# untitled.net
KiCad netlist of a schematic drawn in EAGLE
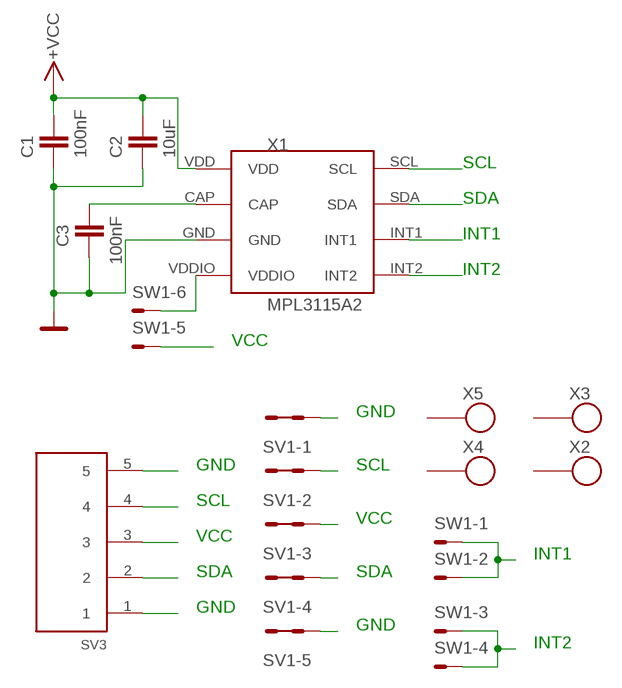
[diagram p0: schematic, sheet 1]

(export (version "E")
  (design (tool "Eeschema 10.0.6"))
  (components
    (comp (ref "C1")
      (value "100nF")
      (footprint "eagle-import:C0805")
      (libsource (lib "eagle-import") (part "C-EUC0805"))
    )
    (comp (ref "C2")
      (value "10uF")
      (footprint "eagle-import:C0805")
      (libsource (lib "eagle-import") (part "C-EUC0805"))
    )
    (comp (ref "C3")
      (value "100nF")
      (footprint "eagle-import:C0805")
      (libsource (lib "eagle-import") (part "C-EUC0805"))
    )
    (comp (ref "SV1")
      (value "MA05-2")
      (footprint "eagle-import:MA05-2")
      (libsource (lib "eagle-import") (part "MA05-2"))
    )
    (comp (ref "SV3")
      (value "SMD_MA05-01")
      (footprint "eagle-import:SMD_MA05-1")
      (libsource (lib "eagle-import") (part "SMD_MA05-01"))
    )
    (comp (ref "SW1")
      (value "MA03-3")
      (footprint "eagle-import:MA03-2")
      (libsource (lib "eagle-import") (part "MA03-3"))
    )
    (comp (ref "X1")
      (value "MPL3115A2")
      (footprint "eagle-import:LGA")
      (libsource (lib "eagle-import") (part "MPL3115A2"))
    )
    (comp (ref "X2")
      (value "SROUB3M")
      (footprint "eagle-import:SROUB3M")
      (libsource (lib "eagle-import") (part "SROUB3M"))
    )
    (comp (ref "X3")
      (value "SROUB3M")
      (footprint "eagle-import:SROUB3M")
      (libsource (lib "eagle-import") (part "SROUB3M"))
    )
    (comp (ref "X4")
      (value "SROUB3M")
      (footprint "eagle-import:SROUB3M")
      (libsource (lib "eagle-import") (part "SROUB3M"))
    )
    (comp (ref "X5")
      (value "SROUB3M")
      (footprint "eagle-import:SROUB3M")
      (libsource (lib "eagle-import") (part "SROUB3M"))
    )
  )
  (nets
    (net (code "1") (name "+VCC") (class "Default")
      (node (ref "C1") (pin "1") (pinfunction "1_1") (pintype "passive"))
      (node (ref "C2") (pin "1") (pinfunction "1_1") (pintype "passive"))
      (node (ref "SV1") (pin "5") (pinfunction "K_5") (pintype "passive"))
      (node (ref "SV1") (pin "6") (pinfunction "K_6") (pintype "passive"))
      (node (ref "SV3") (pin "3") (pinfunction "3_3") (pintype "bidirectional"))
      (node (ref "SW1") (pin "5") (pinfunction "P$1_5") (pintype "passive"))
      (node (ref "X1") (pin "VDD") (pinfunction "VDD_VDD") (pintype "bidirectional"))
    )
    (net (code "2") (name "/INT1") (class "Default")
      (node (ref "SW1") (pin "1") (pinfunction "P$1_1") (pintype "passive"))
      (node (ref "SW1") (pin "2") (pinfunction "P$1_2") (pintype "passive"))
      (node (ref "X1") (pin "INT1") (pinfunction "INT1_INT1") (pintype "bidirectional"))
    )
    (net (code "3") (name "/INT2") (class "Default")
      (node (ref "SW1") (pin "3") (pinfunction "P$1_3") (pintype "passive"))
      (node (ref "SW1") (pin "4") (pinfunction "P$1_4") (pintype "passive"))
      (node (ref "X1") (pin "INT2") (pinfunction "INT2_INT2") (pintype "bidirectional"))
    )
    (net (code "4") (name "/SCL") (class "Default")
      (node (ref "SV1") (pin "3") (pinfunction "K_3") (pintype "passive"))
      (node (ref "SV1") (pin "4") (pinfunction "K_4") (pintype "passive"))
      (node (ref "SV3") (pin "4") (pinfunction "4_4") (pintype "bidirectional"))
      (node (ref "X1") (pin "SCL") (pinfunction "SCL_SCL") (pintype "bidirectional"))
    )
    (net (code "5") (name "/SDA") (class "Default")
      (node (ref "SV1") (pin "7") (pinfunction "K_7") (pintype "passive"))
      (node (ref "SV1") (pin "8") (pinfunction "K_8") (pintype "passive"))
      (node (ref "SV3") (pin "2") (pinfunction "2_2") (pintype "bidirectional"))
      (node (ref "X1") (pin "SDA") (pinfunction "SDA_SDA") (pintype "bidirectional"))
    )
    (net (code "6") (name "GND") (class "Default")
      (node (ref "C1") (pin "2") (pinfunction "2_2") (pintype "passive"))
      (node (ref "C2") (pin "2") (pinfunction "2_2") (pintype "passive"))
      (node (ref "C3") (pin "2") (pinfunction "2_2") (pintype "passive"))
      (node (ref "SV1") (pin "1") (pinfunction "K_1") (pintype "passive"))
      (node (ref "SV1") (pin "10") (pinfunction "K_10") (pintype "passive"))
      (node (ref "SV1") (pin "2") (pinfunction "K_2") (pintype "passive"))
      (node (ref "SV1") (pin "9") (pinfunction "K_9") (pintype "passive"))
      (node (ref "SV3") (pin "1") (pinfunction "1_1") (pintype "bidirectional"))
      (node (ref "SV3") (pin "5") (pinfunction "5_5") (pintype "bidirectional"))
      (node (ref "X1") (pin "GND") (pinfunction "GND_GND") (pintype "bidirectional"))
    )
    (net (code "7") (name "Net-(C3-Pad1)") (class "Default")
      (node (ref "C3") (pin "1") (pinfunction "1_1") (pintype "passive"))
      (node (ref "X1") (pin "CAP") (pinfunction "CAP_CAP") (pintype "bidirectional"))
    )
    (net (code "8") (name "Net-(SW1F-P$1)") (class "Default")
      (node (ref "SW1") (pin "6") (pinfunction "P$1_6") (pintype "passive"))
      (node (ref "X1") (pin "VDDIO") (pinfunction "VDDIO_VDDIO") (pintype "bidirectional"))
    )
    (net (code "9") (name "unconnected-(X2-PadP$1)") (class "Default")
      (node (ref "X2") (pin "P$1") (pinfunction "P$1_P$1") (pintype "bidirectional"))
    )
    (net (code "10") (name "unconnected-(X3-PadP$1)") (class "Default")
      (node (ref "X3") (pin "P$1") (pinfunction "P$1_P$1") (pintype "bidirectional"))
    )
    (net (code "11") (name "unconnected-(X4-PadP$1)") (class "Default")
      (node (ref "X4") (pin "P$1") (pinfunction "P$1_P$1") (pintype "bidirectional"))
    )
    (net (code "12") (name "unconnected-(X5-PadP$1)") (class "Default")
      (node (ref "X5") (pin "P$1") (pinfunction "P$1_P$1") (pintype "bidirectional"))
    )
  )
)
